# Sheet1.net
KiCad netlist of a schematic drawn in Altium Designer
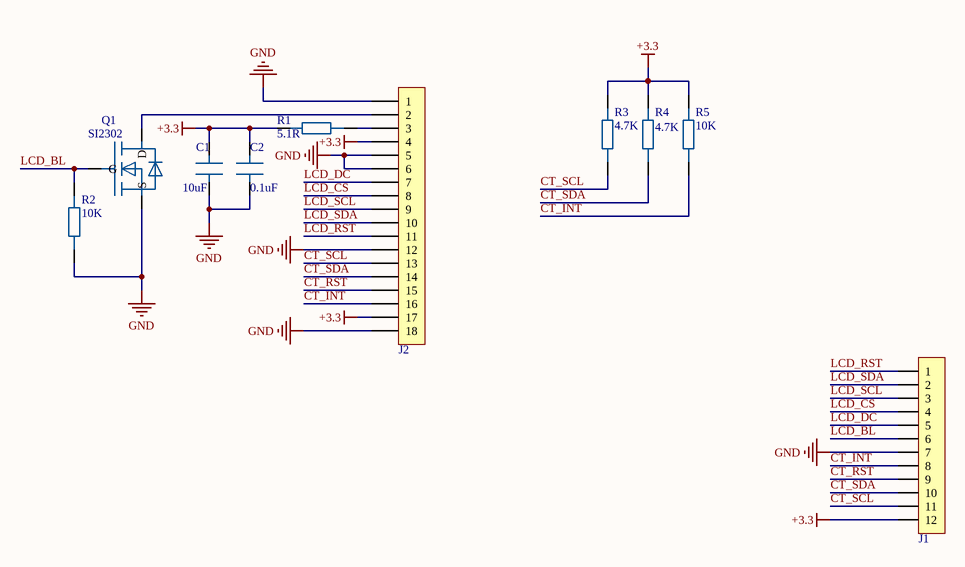
[diagram p0: Sheet1.SchDoc]

(export (version "E")
  (design (tool "Eeschema 10.0.6"))
  (components
    (comp (ref "C1")
      (value "10uF")
      (footprint "0402C")
      (description "电容")
      (libsource (lib "Ares_Xiao_Hui_Lib") (part "Cap"))
    )
    (comp (ref "C2")
      (value "0.1uF")
      (footprint "0402C")
      (description "电容")
      (libsource (lib "Ares_Xiao_Hui_Lib") (part "Cap"))
    )
    (comp (ref "J1")
      (value "CON1X12")
      (footprint "CON1X12 2.54mm")
      (description "接线端子")
      (libsource (lib "Ares_Xiao_Hui_Lib") (part "Handler 1X12"))
    )
    (comp (ref "J2")
      (value "Handler 1X18")
      (footprint "0.5mm 18P 无锁 FPC连接座")
      (description "接线端子")
      (libsource (lib "Ares_Xiao_Hui_Lib") (part "Handler 1X18"))
    )
    (comp (ref "Q1")
      (value "SI2302")
      (footprint "SOT-23")
      (description "N沟道场效应管")
      (libsource (lib "Schlib") (part "NMOS"))
    )
    (comp (ref "R1")
      (value "5.1R")
      (footprint "0402R")
      (description "电阻")
      (libsource (lib "Ares_Xiao_Hui_Lib") (part "Res"))
    )
    (comp (ref "R2")
      (value "10K")
      (footprint "0402R")
      (description "电阻")
      (libsource (lib "Ares_Xiao_Hui_Lib") (part "Res"))
    )
    (comp (ref "R3")
      (value "4.7K")
      (footprint "0402R")
      (description "电阻")
      (libsource (lib "Ares_Xiao_Hui_Lib") (part "Res"))
    )
    (comp (ref "R4")
      (value "4.7K")
      (footprint "0402R")
      (description "电阻")
      (libsource (lib "Ares_Xiao_Hui_Lib") (part "Res"))
    )
    (comp (ref "R5")
      (value "10K")
      (footprint "0402R")
      (description "电阻")
      (libsource (lib "Ares_Xiao_Hui_Lib") (part "Res"))
    )
  )
  (nets
    (net (code "1") (name "+3.3") (class "Default")
      (node (ref "C1") (pin "2") (pinfunction "2_2") (pintype "passive"))
      (node (ref "C2") (pin "2") (pinfunction "2_2") (pintype "passive"))
      (node (ref "J1") (pin "12") (pinfunction "12_12") (pintype "passive"))
      (node (ref "J2") (pin "17") (pinfunction "17_17") (pintype "passive"))
      (node (ref "J2") (pin "4") (pinfunction "4_4") (pintype "passive"))
      (node (ref "R1") (pin "1") (pinfunction "1_1") (pintype "passive"))
      (node (ref "R3") (pin "1") (pinfunction "1_1") (pintype "passive"))
      (node (ref "R4") (pin "1") (pinfunction "1_1") (pintype "passive"))
      (node (ref "R5") (pin "1") (pinfunction "1_1") (pintype "passive"))
    )
    (net (code "2") (name "/CT_INT") (class "Default")
      (node (ref "J1") (pin "8") (pinfunction "8_8") (pintype "passive"))
      (node (ref "J2") (pin "16") (pinfunction "16_16") (pintype "passive"))
      (node (ref "R5") (pin "2") (pinfunction "2_2") (pintype "passive"))
    )
    (net (code "3") (name "/CT_RST") (class "Default")
      (node (ref "J1") (pin "9") (pinfunction "9_9") (pintype "passive"))
      (node (ref "J2") (pin "15") (pinfunction "15_15") (pintype "passive"))
    )
    (net (code "4") (name "/CT_SCL") (class "Default")
      (node (ref "J1") (pin "11") (pinfunction "11_11") (pintype "passive"))
      (node (ref "J2") (pin "13") (pinfunction "13_13") (pintype "passive"))
      (node (ref "R3") (pin "2") (pinfunction "2_2") (pintype "passive"))
    )
    (net (code "5") (name "/CT_SDA") (class "Default")
      (node (ref "J1") (pin "10") (pinfunction "10_10") (pintype "passive"))
      (node (ref "J2") (pin "14") (pinfunction "14_14") (pintype "passive"))
      (node (ref "R4") (pin "2") (pinfunction "2_2") (pintype "passive"))
    )
    (net (code "6") (name "/LCD_BL") (class "Default")
      (node (ref "J1") (pin "6") (pinfunction "6_6") (pintype "passive"))
      (node (ref "Q1") (pin "1") (pinfunction "G_1") (pintype "passive"))
      (node (ref "R2") (pin "1") (pinfunction "1_1") (pintype "passive"))
    )
    (net (code "7") (name "/LCD_CS") (class "Default")
      (node (ref "J1") (pin "4") (pinfunction "4_4") (pintype "passive"))
      (node (ref "J2") (pin "8") (pinfunction "8_8") (pintype "passive"))
    )
    (net (code "8") (name "/LCD_DC") (class "Default")
      (node (ref "J1") (pin "5") (pinfunction "5_5") (pintype "passive"))
      (node (ref "J2") (pin "7") (pinfunction "7_7") (pintype "passive"))
    )
    (net (code "9") (name "/LCD_RST") (class "Default")
      (node (ref "J1") (pin "1") (pinfunction "1_1") (pintype "passive"))
      (node (ref "J2") (pin "11") (pinfunction "11_11") (pintype "passive"))
    )
    (net (code "10") (name "/LCD_SCL") (class "Default")
      (node (ref "J1") (pin "3") (pinfunction "3_3") (pintype "passive"))
      (node (ref "J2") (pin "9") (pinfunction "9_9") (pintype "passive"))
    )
    (net (code "11") (name "/LCD_SDA") (class "Default")
      (node (ref "J1") (pin "2") (pinfunction "2_2") (pintype "passive"))
      (node (ref "J2") (pin "10") (pinfunction "10_10") (pintype "passive"))
    )
    (net (code "12") (name "GND") (class "Default")
      (node (ref "C1") (pin "1") (pinfunction "1_1") (pintype "passive"))
      (node (ref "C2") (pin "1") (pinfunction "1_1") (pintype "passive"))
      (node (ref "J1") (pin "7") (pinfunction "7_7") (pintype "passive"))
      (node (ref "J2") (pin "1") (pinfunction "1_1") (pintype "passive"))
      (node (ref "J2") (pin "12") (pinfunction "12_12") (pintype "passive"))
      (node (ref "J2") (pin "18") (pinfunction "18_18") (pintype "passive"))
      (node (ref "J2") (pin "5") (pinfunction "5_5") (pintype "passive"))
      (node (ref "J2") (pin "6") (pinfunction "6_6") (pintype "passive"))
      (node (ref "Q1") (pin "2") (pinfunction "S_2") (pintype "passive"))
      (node (ref "R2") (pin "2") (pinfunction "2_2") (pintype "passive"))
    )
    (net (code "13") (name "Net-(J2-Pad3)") (class "Default")
      (node (ref "J2") (pin "3") (pinfunction "3_3") (pintype "passive"))
      (node (ref "R1") (pin "2") (pinfunction "2_2") (pintype "passive"))
    )
    (net (code "14") (name "Net-(Q1-D)") (class "Default")
      (node (ref "J2") (pin "2") (pinfunction "2_2") (pintype "passive"))
      (node (ref "Q1") (pin "3") (pinfunction "D_3") (pintype "passive"))
    )
  )
)
